# Camera_IR.net
KiCad netlist of a schematic drawn in EasyEDA
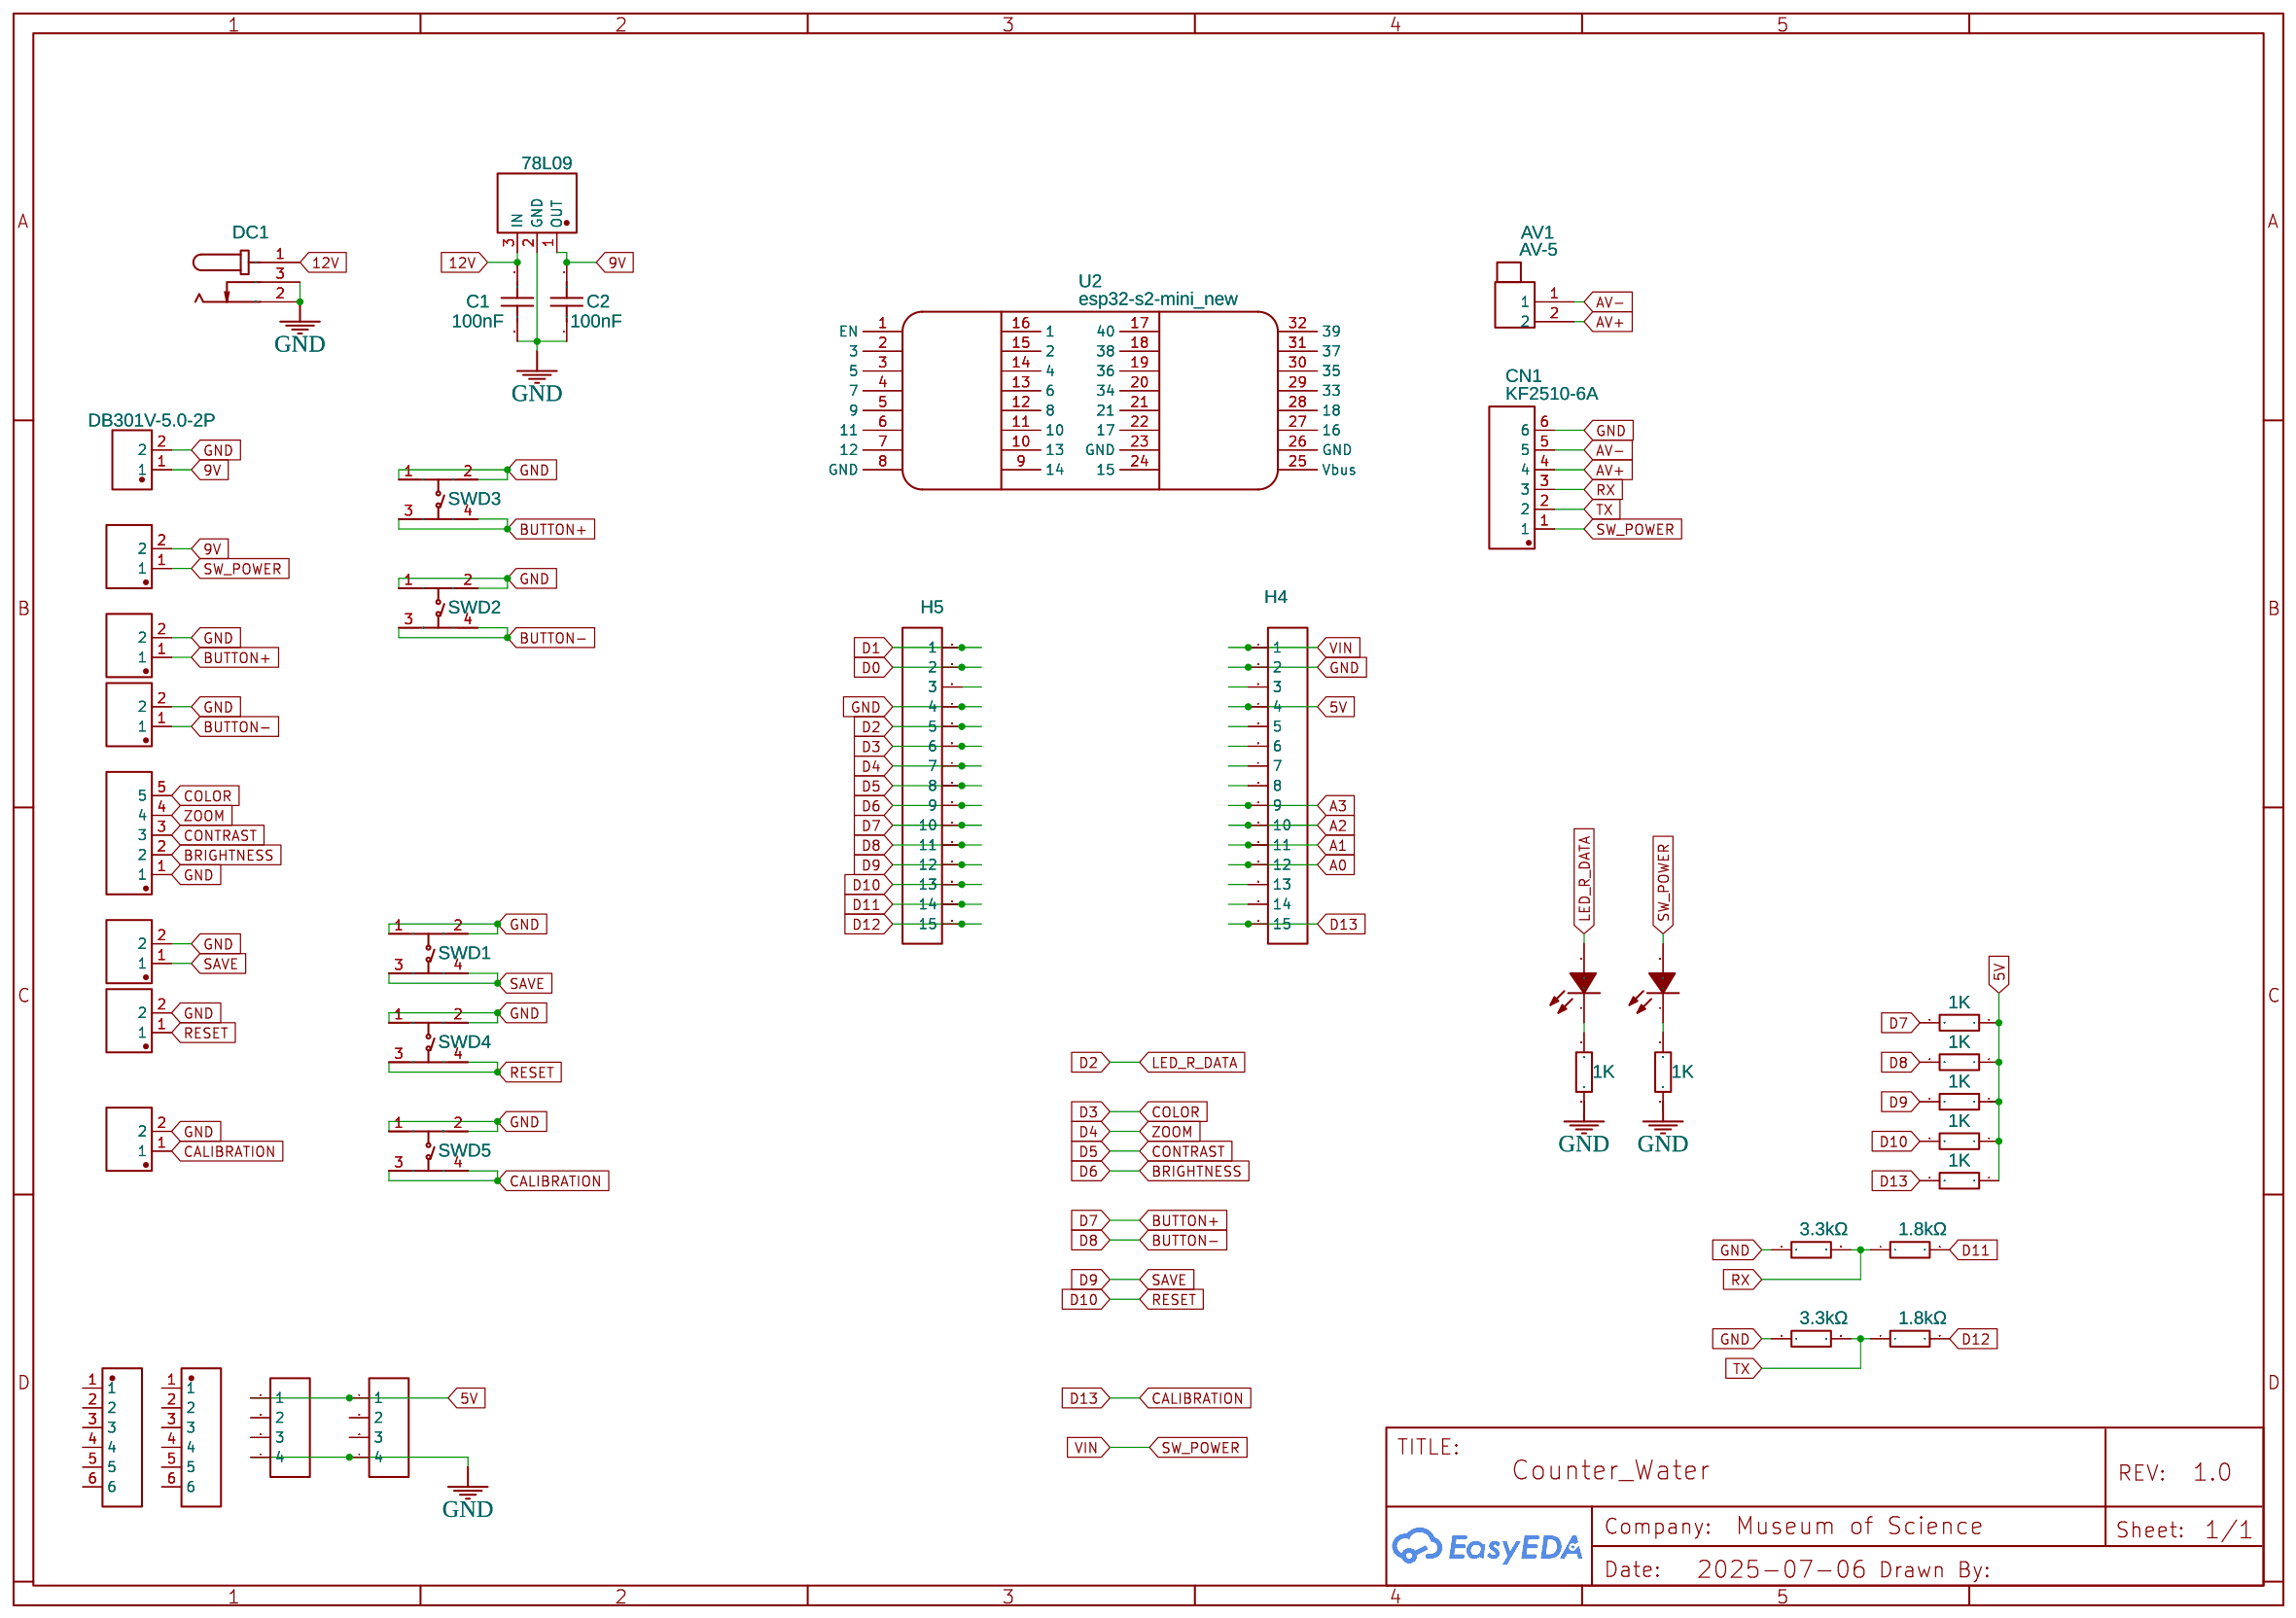
[diagram p0: schematic sheet]

(export (version "E")
  (design (tool "Eeschema 10.0.6"))
  (components
    (comp (ref "AV1")
      (value "AV-5")
      (fields (field (name "Manufacturer") "BOOMELE(博穆精密)"))
      (libsource (lib "") (part "AV-5"))
    )
    (comp (ref "C1")
      (value "100nF")
      (fields
        (field (name "Manufacturer Part") "CC0603KRX7R9BB104")
        (field (name "Manufacturer") "YAGEO(国巨)")
      )
      (libsource (lib "") (part "CC0603KRX7R9BB104"))
    )
    (comp (ref "C2")
      (value "100nF")
      (fields
        (field (name "Manufacturer Part") "CC0603KRX7R9BB104")
        (field (name "Manufacturer") "YAGEO(国巨)")
      )
      (libsource (lib "") (part "CC0603KRX7R9BB104"))
    )
    (comp (ref "CN1")
      (value "KF2510-6A")
      (fields (field (name "Manufacturer Part") "KF2510-6A针座"))
      (libsource (lib "") (part "KF2510-6A"))
    )
    (comp (ref "D7")
      (value "B+")
      (fields (field (name "Manufacturer Part") "KF2510-2A") (field (name "Manufacturer") "BOOMELE"))
      (libsource (lib "") (part "KF2510-2A"))
    )
    (comp (ref "D8")
      (value "B-")
      (fields (field (name "Manufacturer Part") "KF2510-2A") (field (name "Manufacturer") "BOOMELE"))
      (libsource (lib "") (part "KF2510-2A"))
    )
    (comp (ref "D9")
      (value "SAVE")
      (fields (field (name "Manufacturer Part") "KF2510-2A") (field (name "Manufacturer") "BOOMELE"))
      (libsource (lib "") (part "KF2510-2A"))
    )
    (comp (ref "D12")
      (value "RESET")
      (fields (field (name "Manufacturer Part") "KF2510-2A") (field (name "Manufacturer") "BOOMELE"))
      (libsource (lib "") (part "KF2510-2A"))
    )
    (comp (ref "D13")
      (value "FFC")
      (fields (field (name "Manufacturer Part") "KF2510-2A") (field (name "Manufacturer") "BOOMELE"))
      (libsource (lib "") (part "KF2510-2A"))
    )
    (comp (ref "DC1")
      (value "DC")
      (fields (field (name "Manufacturer Part") "DC005-2.0MM") (field (name "Manufacturer") "SOFNG"))
      (libsource (lib "") (part "DC005-2.0MM"))
    )
    (comp (ref "ERL1")
      (value "1K")
      (fields (field (name "Manufacturer Part") "0603WAF1001T5E") (field (name "Manufacturer") "UniOhm"))
      (libsource (lib "") (part "0603WAF1001T5E"))
    )
    (comp (ref "ERL2")
      (value "1K")
      (fields (field (name "Manufacturer Part") "0603WAF1001T5E") (field (name "Manufacturer") "UniOhm"))
      (libsource (lib "") (part "0603WAF1001T5E_1"))
    )
    (comp (ref "ERL4")
      (value "1K")
      (fields (field (name "Manufacturer Part") "0603WAF1001T5E") (field (name "Manufacturer") "UniOhm"))
      (libsource (lib "") (part "0603WAF1001T5E"))
    )
    (comp (ref "ERL6")
      (value "1K")
      (fields (field (name "Manufacturer Part") "0603WAF1001T5E") (field (name "Manufacturer") "UniOhm"))
      (libsource (lib "") (part "0603WAF1001T5E_1"))
    )
    (comp (ref "ERL9")
      (value "1K")
      (fields (field (name "Manufacturer Part") "0603WAF1001T5E") (field (name "Manufacturer") "UniOhm"))
      (libsource (lib "") (part "0603WAF1001T5E_1"))
    )
    (comp (ref "ERL11")
      (value "1K")
      (fields (field (name "Manufacturer Part") "0603WAF1001T5E") (field (name "Manufacturer") "UniOhm"))
      (libsource (lib "") (part "0603WAF1001T5E_1"))
    )
    (comp (ref "ERL12")
      (value "1K")
      (fields (field (name "Manufacturer Part") "0603WAF1001T5E") (field (name "Manufacturer") "UniOhm"))
      (libsource (lib "") (part "0603WAF1001T5E_1"))
    )
    (comp (ref "H4") (value "HDR-F-2.54_1x15") (libsource (lib "") (part "HDR-F-2.54_1x15_1")))
    (comp (ref "H5") (value "HDR-F-2.54_1x15") (libsource (lib "") (part "HDR-F-2.54_1x15")))
    (comp (ref "J6") (value "HDR-M-2.54_1x4") (libsource (lib "") (part "HDR-M-2.54_1x4")))
    (comp (ref "J7") (value "HDR-M-2.54_1x4") (libsource (lib "") (part "HDR-M-2.54_1x4")))
    (comp (ref "LED4")
      (value "KT-0603R")
      (fields (field (name "Manufacturer") "KENTO"))
      (libsource (lib "") (part "KT-0603R"))
    )
    (comp (ref "LED5")
      (value "KT-0603R")
      (fields (field (name "Manufacturer") "KENTO"))
      (libsource (lib "") (part "KT-0603R"))
    )
    (comp (ref "P1")
      (value "KF2510-5A")
      (fields (field (name "Manufacturer Part") "2510-5A") (field (name "Manufacturer") "BOOMELE(博穆精密)"))
      (libsource (lib "") (part "KF2510-5A"))
    )
    (comp (ref "P2")
      (value "H6")
      (fields (field (name "Manufacturer Part") "2.54-1*6P母") (field (name "Manufacturer") "BOOMELE(博穆精密)"))
      (libsource (lib "") (part "Header-Female-2.54_1x6"))
    )
    (comp (ref "P3")
      (value "H6")
      (fields (field (name "Manufacturer Part") "2.54-1*6P母") (field (name "Manufacturer") "BOOMELE(博穆精密)"))
      (libsource (lib "") (part "Header-Female-2.54_1x6"))
    )
    (comp (ref "R1")
      (value "1.8kΩ")
      (fields
        (field (name "Manufacturer Part") "0603WAF1801T5E")
        (field (name "Manufacturer") "UNI-ROYAL(厚声)")
      )
      (libsource (lib "") (part "0603WAF1801T5E"))
    )
    (comp (ref "R2")
      (value "1.8kΩ")
      (fields
        (field (name "Manufacturer Part") "0603WAF1801T5E")
        (field (name "Manufacturer") "UNI-ROYAL(厚声)")
      )
      (libsource (lib "") (part "0603WAF1801T5E"))
    )
    (comp (ref "R3")
      (value "3.3kΩ")
      (fields
        (field (name "Manufacturer Part") "0402WGF3301TCE")
        (field (name "Manufacturer") "UNI-ROYAL(厚声)")
      )
      (libsource (lib "") (part "0402WGF3301TCE"))
    )
    (comp (ref "R4")
      (value "3.3kΩ")
      (fields
        (field (name "Manufacturer Part") "0402WGF3301TCE")
        (field (name "Manufacturer") "UNI-ROYAL(厚声)")
      )
      (libsource (lib "") (part "0402WGF3301TCE"))
    )
    (comp (ref "SWD1")
      (value "TC-6610-7-160G")
      (fields (field (name "Manufacturer") "HCTL(华灿天禄)"))
      (libsource (lib "") (part "TC-6610-7-160G"))
    )
    (comp (ref "SWD2")
      (value "TC-6610-7-160G")
      (fields (field (name "Manufacturer") "HCTL(华灿天禄)"))
      (libsource (lib "") (part "TC-6610-7-160G"))
    )
    (comp (ref "SWD3")
      (value "TC-6610-7-160G")
      (fields (field (name "Manufacturer") "HCTL(华灿天禄)"))
      (libsource (lib "") (part "TC-6610-7-160G"))
    )
    (comp (ref "SWD4")
      (value "TC-6610-7-160G")
      (fields (field (name "Manufacturer") "HCTL(华灿天禄)"))
      (libsource (lib "") (part "TC-6610-7-160G"))
    )
    (comp (ref "SWD5")
      (value "TC-6610-7-160G")
      (fields (field (name "Manufacturer") "HCTL(华灿天禄)"))
      (libsource (lib "") (part "TC-6610-7-160G"))
    )
    (comp (ref "SW_P")
      (value "SW_P")
      (fields (field (name "Manufacturer Part") "KF2510-2A") (field (name "Manufacturer") "BOOMELE"))
      (libsource (lib "") (part "KF2510-2A_1"))
    )
    (comp (ref "U1")
      (value "78L09")
      (fields (field (name "Manufacturer") "CBI(创基)"))
      (libsource (lib "") (part "78L09U 78L09"))
    )
    (comp (ref "U2") (value "esp32-s2-mini_new") (libsource (lib "") (part "esp32-s2-mini_new")))
    (comp (ref "U3")
      (value "DB301V-5.0-2P")
      (fields
        (field (name "Manufacturer Part") "DB301V-5.0-2P-BU-S")
        (field (name "Manufacturer") "DORABO(地博电气)")
      )
      (libsource (lib "") (part "DB301V-5.0-2P"))
    )
  )
  (nets
    (net (code "1") (name "5V") (class "Default")
      (node (ref "ERL11") (pin "1") (pinfunction "1_1") (pintype "input"))
      (node (ref "ERL12") (pin "1") (pinfunction "1_1") (pintype "input"))
      (node (ref "ERL2") (pin "1") (pinfunction "1_1") (pintype "input"))
      (node (ref "ERL6") (pin "1") (pinfunction "1_1") (pintype "input"))
      (node (ref "ERL9") (pin "1") (pinfunction "1_1") (pintype "input"))
      (node (ref "H4") (pin "4") (pinfunction "4_4") (pintype "unspecified"))
      (node (ref "J6") (pin "1") (pinfunction "1_1") (pintype "unspecified"))
      (node (ref "J7") (pin "1") (pinfunction "1_1") (pintype "unspecified"))
    )
    (net (code "2") (name "9V") (class "Default")
      (node (ref "C2") (pin "2") (pinfunction "2_2") (pintype "unspecified"))
      (node (ref "SW_P") (pin "2") (pinfunction "2_2") (pintype "unspecified"))
      (node (ref "U1") (pin "1") (pinfunction "OUT_1") (pintype "unspecified"))
      (node (ref "U3") (pin "1") (pinfunction "1_1") (pintype "unspecified"))
    )
    (net (code "3") (name "12V") (class "Default")
      (node (ref "C1") (pin "2") (pinfunction "2_2") (pintype "unspecified"))
      (node (ref "DC1") (pin "1") (pinfunction "1_1") (pintype "unspecified"))
      (node (ref "U1") (pin "3") (pinfunction "IN_3") (pintype "unspecified"))
    )
    (net (code "4") (name "A0") (class "Default")
      (node (ref "H4") (pin "12") (pinfunction "12_12") (pintype "unspecified"))
    )
    (net (code "5") (name "A1") (class "Default")
      (node (ref "H4") (pin "11") (pinfunction "11_11") (pintype "unspecified"))
    )
    (net (code "6") (name "A2") (class "Default")
      (node (ref "H4") (pin "10") (pinfunction "10_10") (pintype "unspecified"))
    )
    (net (code "7") (name "A3") (class "Default")
      (node (ref "H4") (pin "9") (pinfunction "9_9") (pintype "unspecified"))
    )
    (net (code "8") (name "AV+") (class "Default")
      (node (ref "AV1") (pin "2") (pinfunction "2_2") (pintype "unspecified"))
      (node (ref "CN1") (pin "4") (pinfunction "4_4") (pintype "unspecified"))
    )
    (net (code "9") (name "AV-") (class "Default")
      (node (ref "AV1") (pin "1") (pinfunction "1_1") (pintype "unspecified"))
      (node (ref "CN1") (pin "5") (pinfunction "5_5") (pintype "unspecified"))
    )
    (net (code "10") (name "BRIGHTNESS") (class "Default")
      (node (ref "H5") (pin "9") (pinfunction "9_9") (pintype "unspecified"))
      (node (ref "P1") (pin "2") (pinfunction "2_2") (pintype "unspecified"))
    )
    (net (code "11") (name "BUTTON+") (class "Default")
      (node (ref "D7") (pin "1") (pinfunction "1_1") (pintype "unspecified"))
      (node (ref "ERL6") (pin "2") (pinfunction "2_2") (pintype "input"))
      (node (ref "H5") (pin "10") (pinfunction "10_10") (pintype "unspecified"))
      (node (ref "SWD3") (pin "3") (pinfunction "3_3") (pintype "unspecified"))
      (node (ref "SWD3") (pin "4") (pinfunction "4_4") (pintype "unspecified"))
    )
    (net (code "12") (name "BUTTON-") (class "Default")
      (node (ref "D8") (pin "1") (pinfunction "1_1") (pintype "unspecified"))
      (node (ref "ERL11") (pin "2") (pinfunction "2_2") (pintype "input"))
      (node (ref "H5") (pin "11") (pinfunction "11_11") (pintype "unspecified"))
      (node (ref "SWD2") (pin "3") (pinfunction "3_3") (pintype "unspecified"))
      (node (ref "SWD2") (pin "4") (pinfunction "4_4") (pintype "unspecified"))
    )
    (net (code "13") (name "CALIBRATION") (class "Default")
      (node (ref "D13") (pin "1") (pinfunction "1_1") (pintype "unspecified"))
      (node (ref "ERL2") (pin "2") (pinfunction "2_2") (pintype "input"))
      (node (ref "H4") (pin "15") (pinfunction "15_15") (pintype "unspecified"))
      (node (ref "SWD5") (pin "3") (pinfunction "3_3") (pintype "unspecified"))
      (node (ref "SWD5") (pin "4") (pinfunction "4_4") (pintype "unspecified"))
    )
    (net (code "14") (name "COLOR") (class "Default")
      (node (ref "H5") (pin "6") (pinfunction "6_6") (pintype "unspecified"))
      (node (ref "P1") (pin "5") (pinfunction "5_5") (pintype "unspecified"))
    )
    (net (code "15") (name "CONTRAST") (class "Default")
      (node (ref "H5") (pin "8") (pinfunction "8_8") (pintype "unspecified"))
      (node (ref "P1") (pin "3") (pinfunction "3_3") (pintype "unspecified"))
    )
    (net (code "16") (name "D0") (class "Default")
      (node (ref "H5") (pin "2") (pinfunction "2_2") (pintype "unspecified"))
    )
    (net (code "17") (name "D1") (class "Default")
      (node (ref "H5") (pin "1") (pinfunction "1_1") (pintype "unspecified"))
    )
    (net (code "18") (name "D2") (class "Default")
      (node (ref "H5") (pin "5") (pinfunction "5_5") (pintype "unspecified"))
      (node (ref "LED5") (pin "2") (pinfunction "A_2") (pintype "unspecified"))
    )
    (net (code "19") (name "D4") (class "Default")
      (node (ref "H5") (pin "7") (pinfunction "7_7") (pintype "unspecified"))
      (node (ref "P1") (pin "4") (pinfunction "4_4") (pintype "unspecified"))
    )
    (net (code "20") (name "D9") (class "Default")
      (node (ref "D9") (pin "1") (pinfunction "1_1") (pintype "unspecified"))
      (node (ref "ERL9") (pin "2") (pinfunction "2_2") (pintype "input"))
      (node (ref "H5") (pin "12") (pinfunction "12_12") (pintype "unspecified"))
      (node (ref "SWD1") (pin "3") (pinfunction "3_3") (pintype "unspecified"))
      (node (ref "SWD1") (pin "4") (pinfunction "4_4") (pintype "unspecified"))
    )
    (net (code "21") (name "D10") (class "Default")
      (node (ref "D12") (pin "1") (pinfunction "1_1") (pintype "unspecified"))
      (node (ref "ERL12") (pin "2") (pinfunction "2_2") (pintype "input"))
      (node (ref "H5") (pin "13") (pinfunction "13_13") (pintype "unspecified"))
      (node (ref "SWD4") (pin "3") (pinfunction "3_3") (pintype "unspecified"))
      (node (ref "SWD4") (pin "4") (pinfunction "4_4") (pintype "unspecified"))
    )
    (net (code "22") (name "D11") (class "Default")
      (node (ref "H5") (pin "14") (pinfunction "14_14") (pintype "unspecified"))
      (node (ref "R1") (pin "2") (pinfunction "2_2") (pintype "input"))
    )
    (net (code "23") (name "D12") (class "Default")
      (node (ref "H5") (pin "15") (pinfunction "15_15") (pintype "unspecified"))
      (node (ref "R2") (pin "2") (pinfunction "2_2") (pintype "input"))
    )
    (net (code "24") (name "GND") (class "Default")
      (node (ref "C1") (pin "1") (pinfunction "1_1") (pintype "unspecified"))
      (node (ref "C2") (pin "1") (pinfunction "1_1") (pintype "unspecified"))
      (node (ref "CN1") (pin "6") (pinfunction "6_6") (pintype "unspecified"))
      (node (ref "D12") (pin "2") (pinfunction "2_2") (pintype "unspecified"))
      (node (ref "D13") (pin "2") (pinfunction "2_2") (pintype "unspecified"))
      (node (ref "D7") (pin "2") (pinfunction "2_2") (pintype "unspecified"))
      (node (ref "D8") (pin "2") (pinfunction "2_2") (pintype "unspecified"))
      (node (ref "D9") (pin "2") (pinfunction "2_2") (pintype "unspecified"))
      (node (ref "DC1") (pin "2") (pinfunction "2_2") (pintype "unspecified"))
      (node (ref "DC1") (pin "3") (pinfunction "3_3") (pintype "unspecified"))
      (node (ref "ERL1") (pin "1") (pinfunction "1_1") (pintype "input"))
      (node (ref "ERL4") (pin "1") (pinfunction "1_1") (pintype "input"))
      (node (ref "H4") (pin "2") (pinfunction "2_2") (pintype "unspecified"))
      (node (ref "H5") (pin "4") (pinfunction "4_4") (pintype "unspecified"))
      (node (ref "J6") (pin "4") (pinfunction "4_4") (pintype "unspecified"))
      (node (ref "J7") (pin "4") (pinfunction "4_4") (pintype "unspecified"))
      (node (ref "P1") (pin "1") (pinfunction "1_1") (pintype "unspecified"))
      (node (ref "R3") (pin "1") (pinfunction "1_1") (pintype "input"))
      (node (ref "R4") (pin "1") (pinfunction "1_1") (pintype "input"))
      (node (ref "SWD1") (pin "1") (pinfunction "1_1") (pintype "unspecified"))
      (node (ref "SWD1") (pin "2") (pinfunction "2_2") (pintype "unspecified"))
      (node (ref "SWD2") (pin "1") (pinfunction "1_1") (pintype "unspecified"))
      (node (ref "SWD2") (pin "2") (pinfunction "2_2") (pintype "unspecified"))
      (node (ref "SWD3") (pin "1") (pinfunction "1_1") (pintype "unspecified"))
      (node (ref "SWD3") (pin "2") (pinfunction "2_2") (pintype "unspecified"))
      (node (ref "SWD4") (pin "1") (pinfunction "1_1") (pintype "unspecified"))
      (node (ref "SWD4") (pin "2") (pinfunction "2_2") (pintype "unspecified"))
      (node (ref "SWD5") (pin "1") (pinfunction "1_1") (pintype "unspecified"))
      (node (ref "SWD5") (pin "2") (pinfunction "2_2") (pintype "unspecified"))
      (node (ref "U1") (pin "2") (pinfunction "GND_2") (pintype "unspecified"))
      (node (ref "U3") (pin "2") (pinfunction "2_2") (pintype "unspecified"))
    )
    (net (code "25") (name "Net-(LED4-K)") (class "Default")
      (node (ref "ERL4") (pin "2") (pinfunction "2_2") (pintype "input"))
      (node (ref "LED4") (pin "1") (pinfunction "K_1") (pintype "unspecified"))
    )
    (net (code "26") (name "Net-(LED5-K)") (class "Default")
      (node (ref "ERL1") (pin "2") (pinfunction "2_2") (pintype "input"))
      (node (ref "LED5") (pin "1") (pinfunction "K_1") (pintype "unspecified"))
    )
    (net (code "27") (name "RX") (class "Default")
      (node (ref "CN1") (pin "3") (pinfunction "3_3") (pintype "unspecified"))
      (node (ref "R1") (pin "1") (pinfunction "1_1") (pintype "input"))
      (node (ref "R3") (pin "2") (pinfunction "2_2") (pintype "input"))
    )
    (net (code "28") (name "SW_POWER") (class "Default")
      (node (ref "CN1") (pin "1") (pinfunction "1_1") (pintype "unspecified"))
      (node (ref "H4") (pin "1") (pinfunction "1_1") (pintype "unspecified"))
      (node (ref "LED4") (pin "2") (pinfunction "A_2") (pintype "unspecified"))
      (node (ref "SW_P") (pin "1") (pinfunction "1_1") (pintype "unspecified"))
    )
    (net (code "29") (name "TX") (class "Default")
      (node (ref "CN1") (pin "2") (pinfunction "2_2") (pintype "unspecified"))
      (node (ref "R2") (pin "1") (pinfunction "1_1") (pintype "input"))
      (node (ref "R4") (pin "2") (pinfunction "2_2") (pintype "input"))
    )
    (net (code "30") (name "unconnected-(H4-Pad3)") (class "Default")
      (node (ref "H4") (pin "3") (pinfunction "3_3") (pintype "unspecified"))
    )
    (net (code "31") (name "unconnected-(H4-Pad5)") (class "Default")
      (node (ref "H4") (pin "5") (pinfunction "5_5") (pintype "unspecified"))
    )
    (net (code "32") (name "unconnected-(H4-Pad6)") (class "Default")
      (node (ref "H4") (pin "6") (pinfunction "6_6") (pintype "unspecified"))
    )
    (net (code "33") (name "unconnected-(H4-Pad7)") (class "Default")
      (node (ref "H4") (pin "7") (pinfunction "7_7") (pintype "unspecified"))
    )
    (net (code "34") (name "unconnected-(H4-Pad8)") (class "Default")
      (node (ref "H4") (pin "8") (pinfunction "8_8") (pintype "unspecified"))
    )
    (net (code "35") (name "unconnected-(H4-Pad13)") (class "Default")
      (node (ref "H4") (pin "13") (pinfunction "13_13") (pintype "unspecified"))
    )
    (net (code "36") (name "unconnected-(H4-Pad14)") (class "Default")
      (node (ref "H4") (pin "14") (pinfunction "14_14") (pintype "unspecified"))
    )
    (net (code "37") (name "unconnected-(H5-Pad3)") (class "Default")
      (node (ref "H5") (pin "3") (pinfunction "3_3") (pintype "unspecified"))
    )
    (net (code "38") (name "unconnected-(J6-Pad2)") (class "Default")
      (node (ref "J6") (pin "2") (pinfunction "2_2") (pintype "unspecified"))
    )
    (net (code "39") (name "unconnected-(J6-Pad3)") (class "Default")
      (node (ref "J6") (pin "3") (pinfunction "3_3") (pintype "unspecified"))
    )
    (net (code "40") (name "unconnected-(J7-Pad2)") (class "Default")
      (node (ref "J7") (pin "2") (pinfunction "2_2") (pintype "unspecified"))
    )
    (net (code "41") (name "unconnected-(J7-Pad3)") (class "Default")
      (node (ref "J7") (pin "3") (pinfunction "3_3") (pintype "unspecified"))
    )
    (net (code "42") (name "unconnected-(P2-Pad1)") (class "Default")
      (node (ref "P2") (pin "1") (pinfunction "1_1") (pintype "unspecified"))
    )
    (net (code "43") (name "unconnected-(P2-Pad2)") (class "Default")
      (node (ref "P2") (pin "2") (pinfunction "2_2") (pintype "unspecified"))
    )
    (net (code "44") (name "unconnected-(P2-Pad3)") (class "Default")
      (node (ref "P2") (pin "3") (pinfunction "3_3") (pintype "unspecified"))
    )
    (net (code "45") (name "unconnected-(P2-Pad4)") (class "Default")
      (node (ref "P2") (pin "4") (pinfunction "4_4") (pintype "unspecified"))
    )
    (net (code "46") (name "unconnected-(P2-Pad5)") (class "Default")
      (node (ref "P2") (pin "5") (pinfunction "5_5") (pintype "unspecified"))
    )
    (net (code "47") (name "unconnected-(P2-Pad6)") (class "Default")
      (node (ref "P2") (pin "6") (pinfunction "6_6") (pintype "unspecified"))
    )
    (net (code "48") (name "unconnected-(P3-Pad1)") (class "Default")
      (node (ref "P3") (pin "1") (pinfunction "1_1") (pintype "unspecified"))
    )
    (net (code "49") (name "unconnected-(P3-Pad2)") (class "Default")
      (node (ref "P3") (pin "2") (pinfunction "2_2") (pintype "unspecified"))
    )
    (net (code "50") (name "unconnected-(P3-Pad3)") (class "Default")
      (node (ref "P3") (pin "3") (pinfunction "3_3") (pintype "unspecified"))
    )
    (net (code "51") (name "unconnected-(P3-Pad4)") (class "Default")
      (node (ref "P3") (pin "4") (pinfunction "4_4") (pintype "unspecified"))
    )
    (net (code "52") (name "unconnected-(P3-Pad5)") (class "Default")
      (node (ref "P3") (pin "5") (pinfunction "5_5") (pintype "unspecified"))
    )
    (net (code "53") (name "unconnected-(P3-Pad6)") (class "Default")
      (node (ref "P3") (pin "6") (pinfunction "6_6") (pintype "unspecified"))
    )
    (net (code "54") (name "unconnected-(U2-1-Pad16)") (class "Default")
      (node (ref "U2") (pin "16") (pinfunction "1_16") (pintype "unspecified"))
    )
    (net (code "55") (name "unconnected-(U2-2-Pad15)") (class "Default")
      (node (ref "U2") (pin "15") (pinfunction "2_15") (pintype "unspecified"))
    )
    (net (code "56") (name "unconnected-(U2-3-Pad2)") (class "Default")
      (node (ref "U2") (pin "2") (pinfunction "3_2") (pintype "unspecified"))
    )
    (net (code "57") (name "unconnected-(U2-4-Pad14)") (class "Default")
      (node (ref "U2") (pin "14") (pinfunction "4_14") (pintype "unspecified"))
    )
    (net (code "58") (name "unconnected-(U2-5-Pad3)") (class "Default")
      (node (ref "U2") (pin "3") (pinfunction "5_3") (pintype "unspecified"))
    )
    (net (code "59") (name "unconnected-(U2-6-Pad13)") (class "Default")
      (node (ref "U2") (pin "13") (pinfunction "6_13") (pintype "unspecified"))
    )
    (net (code "60") (name "unconnected-(U2-7-Pad4)") (class "Default")
      (node (ref "U2") (pin "4") (pinfunction "7_4") (pintype "unspecified"))
    )
    (net (code "61") (name "unconnected-(U2-8-Pad12)") (class "Default")
      (node (ref "U2") (pin "12") (pinfunction "8_12") (pintype "unspecified"))
    )
    (net (code "62") (name "unconnected-(U2-9-Pad5)") (class "Default")
      (node (ref "U2") (pin "5") (pinfunction "9_5") (pintype "unspecified"))
    )
    (net (code "63") (name "unconnected-(U2-10-Pad11)") (class "Default")
      (node (ref "U2") (pin "11") (pinfunction "10_11") (pintype "unspecified"))
    )
    (net (code "64") (name "unconnected-(U2-11-Pad6)") (class "Default")
      (node (ref "U2") (pin "6") (pinfunction "11_6") (pintype "unspecified"))
    )
    (net (code "65") (name "unconnected-(U2-12-Pad7)") (class "Default")
      (node (ref "U2") (pin "7") (pinfunction "12_7") (pintype "unspecified"))
    )
    (net (code "66") (name "unconnected-(U2-13-Pad10)") (class "Default")
      (node (ref "U2") (pin "10") (pinfunction "13_10") (pintype "unspecified"))
    )
    (net (code "67") (name "unconnected-(U2-14-Pad9)") (class "Default")
      (node (ref "U2") (pin "9") (pinfunction "14_9") (pintype "unspecified"))
    )
    (net (code "68") (name "unconnected-(U2-15-Pad24)") (class "Default")
      (node (ref "U2") (pin "24") (pinfunction "15_24") (pintype "unspecified"))
    )
    (net (code "69") (name "unconnected-(U2-16-Pad27)") (class "Default")
      (node (ref "U2") (pin "27") (pinfunction "16_27") (pintype "unspecified"))
    )
    (net (code "70") (name "unconnected-(U2-17-Pad22)") (class "Default")
      (node (ref "U2") (pin "22") (pinfunction "17_22") (pintype "unspecified"))
    )
    (net (code "71") (name "unconnected-(U2-18-Pad28)") (class "Default")
      (node (ref "U2") (pin "28") (pinfunction "18_28") (pintype "unspecified"))
    )
    (net (code "72") (name "unconnected-(U2-33-Pad29)") (class "Default")
      (node (ref "U2") (pin "29") (pinfunction "33_29") (pintype "unspecified"))
    )
    (net (code "73") (name "unconnected-(U2-34-Pad20)") (class "Default")
      (node (ref "U2") (pin "20") (pinfunction "34_20") (pintype "unspecified"))
    )
    (net (code "74") (name "unconnected-(U2-35-Pad30)") (class "Default")
      (node (ref "U2") (pin "30") (pinfunction "35_30") (pintype "unspecified"))
    )
    (net (code "75") (name "unconnected-(U2-36-Pad19)") (class "Default")
      (node (ref "U2") (pin "19") (pinfunction "36_19") (pintype "unspecified"))
    )
    (net (code "76") (name "unconnected-(U2-37-Pad31)") (class "Default")
      (node (ref "U2") (pin "31") (pinfunction "37_31") (pintype "unspecified"))
    )
    (net (code "77") (name "unconnected-(U2-38-Pad18)") (class "Default")
      (node (ref "U2") (pin "18") (pinfunction "38_18") (pintype "unspecified"))
    )
    (net (code "78") (name "unconnected-(U2-39-Pad32)") (class "Default")
      (node (ref "U2") (pin "32") (pinfunction "39_32") (pintype "unspecified"))
    )
    (net (code "79") (name "unconnected-(U2-40-Pad17)") (class "Default")
      (node (ref "U2") (pin "17") (pinfunction "40_17") (pintype "unspecified"))
    )
    (net (code "80") (name "unconnected-(U2-EN-Pad1)") (class "Default")
      (node (ref "U2") (pin "1") (pinfunction "EN_1") (pintype "unspecified"))
    )
    (net (code "81") (name "unconnected-(U2-GND-Pad8)") (class "Default")
      (node (ref "U2") (pin "8") (pinfunction "GND_8") (pintype "unspecified"))
    )
    (net (code "82") (name "unconnected-(U2-GND-Pad23)") (class "Default")
      (node (ref "U2") (pin "23") (pinfunction "GND_23") (pintype "unspecified"))
    )
    (net (code "83") (name "unconnected-(U2-GND-Pad26)") (class "Default")
      (node (ref "U2") (pin "26") (pinfunction "GND_26") (pintype "unspecified"))
    )
    (net (code "84") (name "unconnected-(U2-Pad21)") (class "Default")
      (node (ref "U2") (pin "21") (pinfunction "21_21") (pintype "unspecified"))
    )
    (net (code "85") (name "unconnected-(U2-Vbus-Pad25)") (class "Default")
      (node (ref "U2") (pin "25") (pinfunction "Vbus_25") (pintype "unspecified"))
    )
  )
)
